# RasPi_Data_Hat.net
KiCad netlist of a schematic drawn in EAGLE
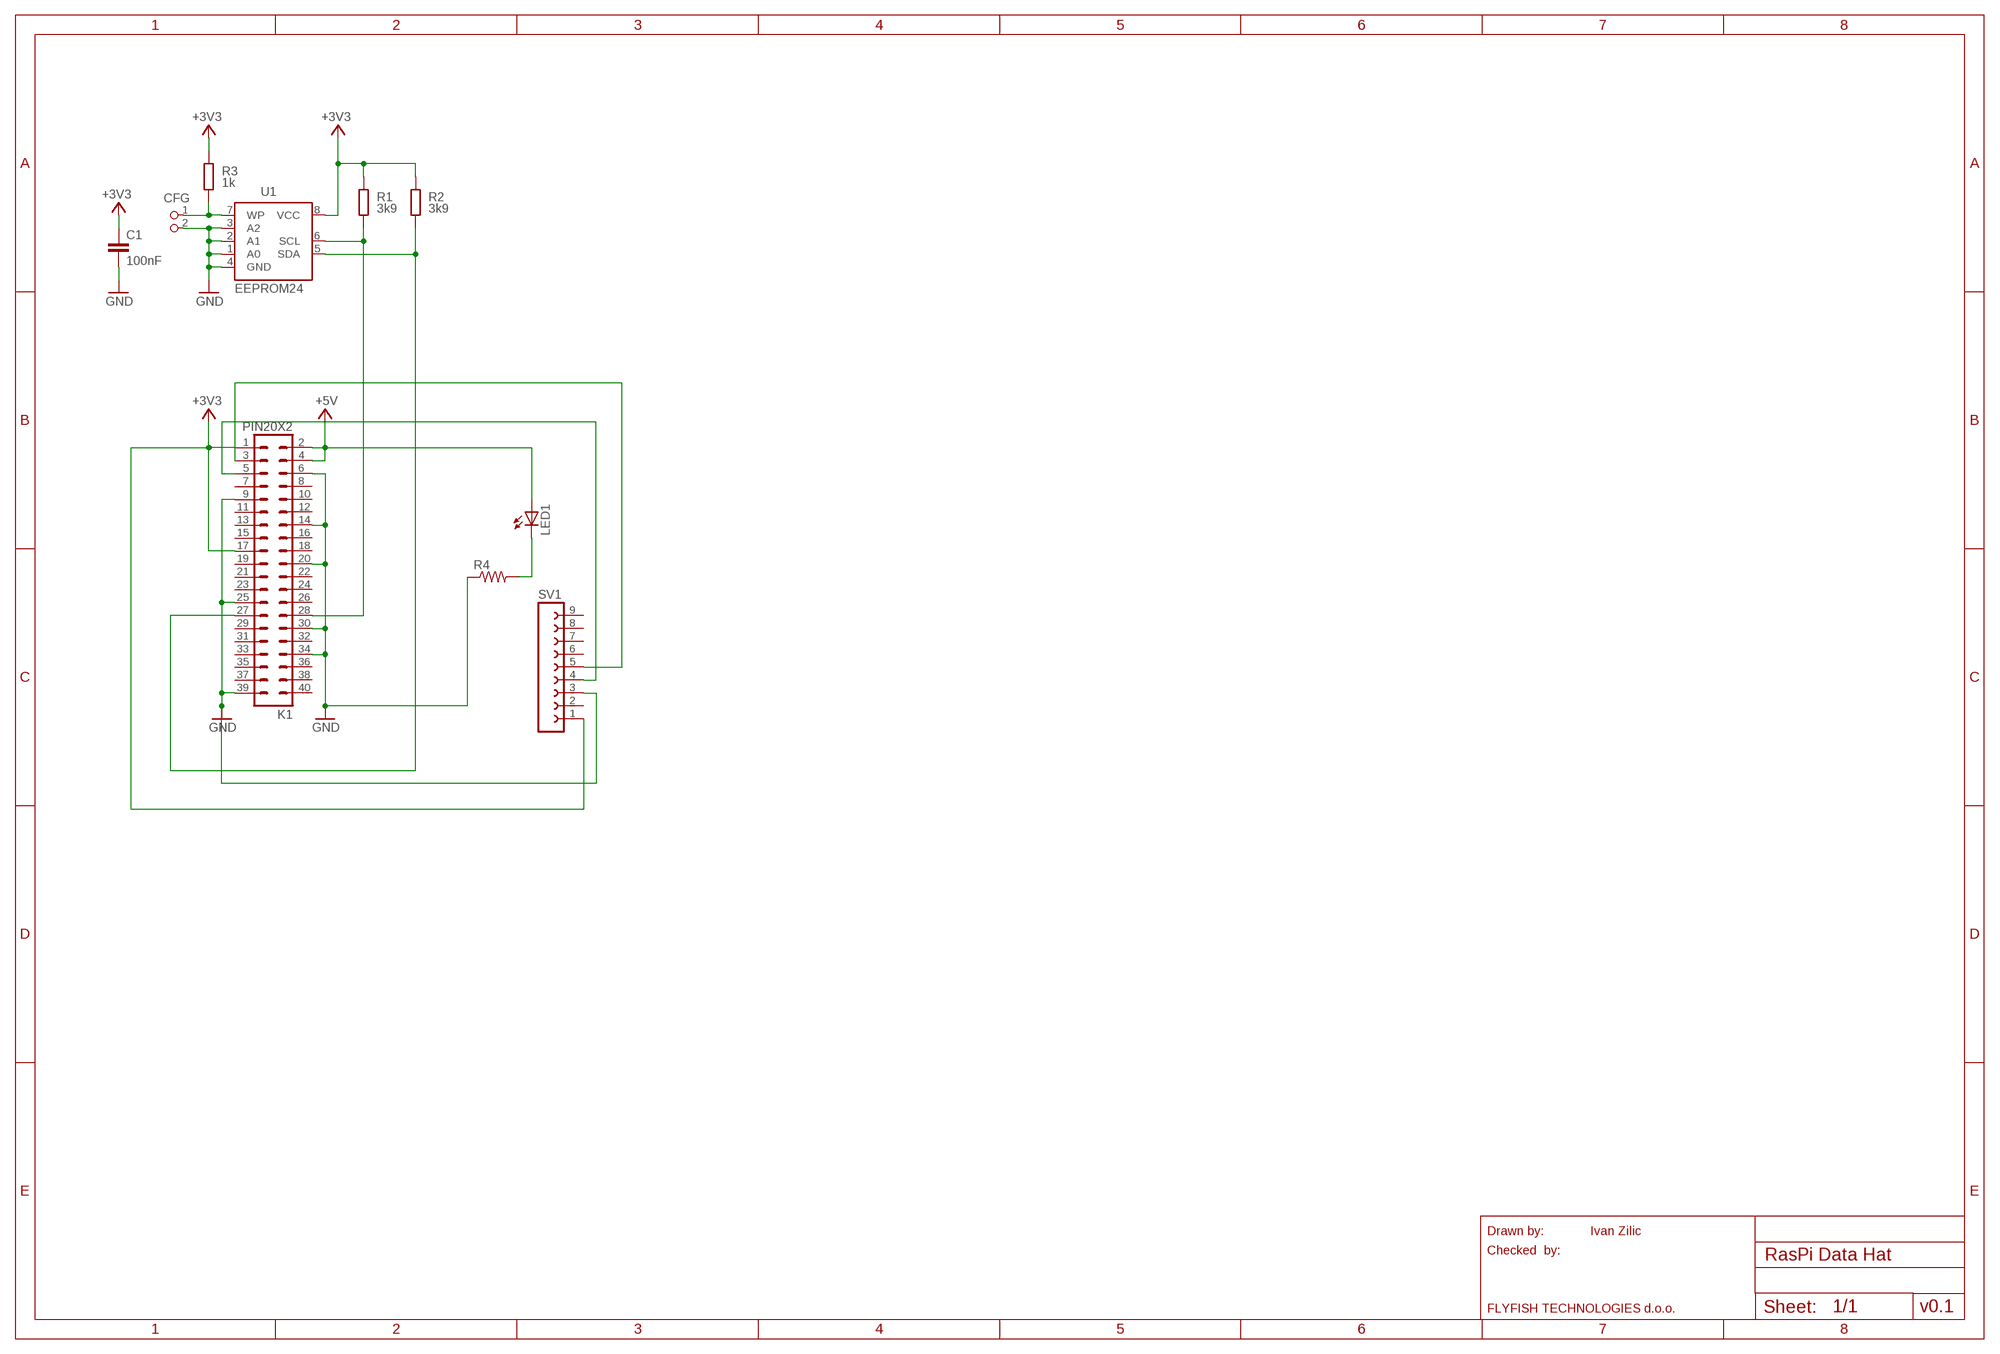
[diagram p0: schematic, sheet 1]

(export (version "E")
  (design (tool "Eeschema 10.0.6"))
  (components
    (comp (ref "C1")
      (value "100nF")
      (footprint "eagle-import:C0805K")
      (libsource (lib "eagle-import") (part "C-EUC0805K"))
    )
    (comp (ref "CFG")
      (value "PIN2_100")
      (footprint "eagle-import:PIN_W_2")
      (libsource (lib "eagle-import") (part "PIN2_100"))
    )
    (comp (ref "K1")
      (value "PIN20X2")
      (footprint "eagle-import:PIN_20X2")
      (libsource (lib "eagle-import") (part "PIN20X2"))
    )
    (comp (ref "LED1")
      (value "LED3MM")
      (footprint "eagle-import:LED3MM")
      (libsource (lib "eagle-import") (part "LED3MM"))
    )
    (comp (ref "R1")
      (value "3k9")
      (footprint "eagle-import:M0805")
      (fields (field (name "TOLERANCE") "5%"))
      (libsource (lib "eagle-import") (part "R-EU_M0805"))
    )
    (comp (ref "R2")
      (value "3k9")
      (footprint "eagle-import:M0805")
      (fields (field (name "TOLERANCE") "5%"))
      (libsource (lib "eagle-import") (part "R-EU_M0805"))
    )
    (comp (ref "R3")
      (value "1k")
      (footprint "eagle-import:M0805")
      (fields (field (name "TOLERANCE") "5%"))
      (libsource (lib "eagle-import") (part "R-EU_M0805"))
    )
    (comp (ref "R4")
      (value "R-US_0204/5")
      (footprint "eagle-import:0204_5")
      (libsource (lib "eagle-import") (part "R-US_0204/5"))
    )
    (comp (ref "SV1")
      (value "FE09-1")
      (footprint "eagle-import:FE09")
      (libsource (lib "eagle-import") (part "FE09-1"))
    )
    (comp (ref "U1")
      (value "EEPROM24")
      (footprint "eagle-import:SOIC8")
      (libsource (lib "eagle-import") (part "EEPROM24"))
    )
  )
  (nets
    (net (code "1") (name "+3V3") (class "Default")
      (node (ref "C1") (pin "1") (pinfunction "1_1") (pintype "passive"))
      (node (ref "K1") (pin "1") (pinfunction "1_1") (pintype "passive"))
      (node (ref "K1") (pin "17") (pinfunction "17_17") (pintype "passive"))
      (node (ref "R1") (pin "2") (pinfunction "2_2") (pintype "passive"))
      (node (ref "R2") (pin "2") (pinfunction "2_2") (pintype "passive"))
      (node (ref "R3") (pin "2") (pinfunction "2_2") (pintype "passive"))
      (node (ref "SV1") (pin "1") (pinfunction "1_1") (pintype "passive"))
      (node (ref "U1") (pin "8") (pinfunction "VCC_8") (pintype "power_in"))
    )
    (net (code "2") (name "+5V") (class "Default")
      (node (ref "K1") (pin "2") (pinfunction "2_2") (pintype "passive"))
      (node (ref "K1") (pin "4") (pinfunction "4_4") (pintype "passive"))
      (node (ref "LED1") (pin "A") (pinfunction "A_A") (pintype "passive"))
    )
    (net (code "3") (name "GND") (class "Default")
      (node (ref "C1") (pin "2") (pinfunction "2_2") (pintype "passive"))
      (node (ref "CFG") (pin "2") (pinfunction "2_2") (pintype "passive"))
      (node (ref "K1") (pin "14") (pinfunction "14_14") (pintype "passive"))
      (node (ref "K1") (pin "20") (pinfunction "20_20") (pintype "passive"))
      (node (ref "K1") (pin "25") (pinfunction "25_25") (pintype "passive"))
      (node (ref "K1") (pin "30") (pinfunction "30_30") (pintype "passive"))
      (node (ref "K1") (pin "34") (pinfunction "34_34") (pintype "passive"))
      (node (ref "K1") (pin "39") (pinfunction "39_39") (pintype "passive"))
      (node (ref "K1") (pin "6") (pinfunction "6_6") (pintype "passive"))
      (node (ref "K1") (pin "9") (pinfunction "9_9") (pintype "passive"))
      (node (ref "R4") (pin "1") (pinfunction "1_1") (pintype "passive"))
      (node (ref "SV1") (pin "3") (pinfunction "3_3") (pintype "passive"))
      (node (ref "U1") (pin "1") (pinfunction "A0_1") (pintype "input"))
      (node (ref "U1") (pin "2") (pinfunction "A1_2") (pintype "input"))
      (node (ref "U1") (pin "3") (pinfunction "A2_3") (pintype "input"))
      (node (ref "U1") (pin "4") (pinfunction "GND_4") (pintype "power_in"))
    )
    (net (code "4") (name "Net-(K1-Pad3)") (class "Default")
      (node (ref "K1") (pin "3") (pinfunction "3_3") (pintype "passive"))
      (node (ref "SV1") (pin "5") (pinfunction "5_5") (pintype "passive"))
    )
    (net (code "5") (name "Net-(K1-Pad5)") (class "Default")
      (node (ref "K1") (pin "5") (pinfunction "5_5") (pintype "passive"))
      (node (ref "SV1") (pin "4") (pinfunction "4_4") (pintype "passive"))
    )
    (net (code "6") (name "Net-(LED1-C)") (class "Default")
      (node (ref "LED1") (pin "K") (pinfunction "C_K") (pintype "passive"))
      (node (ref "R4") (pin "2") (pinfunction "2_2") (pintype "passive"))
    )
    (net (code "7") (name "Net-(U1-SCL)") (class "Default")
      (node (ref "K1") (pin "28") (pinfunction "28_28") (pintype "passive"))
      (node (ref "R1") (pin "1") (pinfunction "1_1") (pintype "passive"))
      (node (ref "U1") (pin "6") (pinfunction "SCL_6") (pintype "input"))
    )
    (net (code "8") (name "Net-(U1-SDA)") (class "Default")
      (node (ref "K1") (pin "27") (pinfunction "27_27") (pintype "passive"))
      (node (ref "R2") (pin "1") (pinfunction "1_1") (pintype "passive"))
      (node (ref "U1") (pin "5") (pinfunction "SDA_5") (pintype "bidirectional"))
    )
    (net (code "9") (name "Net-(U1-WP)") (class "Default")
      (node (ref "CFG") (pin "1") (pinfunction "1_1") (pintype "passive"))
      (node (ref "R3") (pin "1") (pinfunction "1_1") (pintype "passive"))
      (node (ref "U1") (pin "7") (pinfunction "WP_7") (pintype "input"))
    )
    (net (code "10") (name "unconnected-(K1-Pad7)") (class "Default")
      (node (ref "K1") (pin "7") (pinfunction "7_7") (pintype "passive"))
    )
    (net (code "11") (name "unconnected-(K1-Pad8)") (class "Default")
      (node (ref "K1") (pin "8") (pinfunction "8_8") (pintype "passive"))
    )
    (net (code "12") (name "unconnected-(K1-Pad10)") (class "Default")
      (node (ref "K1") (pin "10") (pinfunction "10_10") (pintype "passive"))
    )
    (net (code "13") (name "unconnected-(K1-Pad11)") (class "Default")
      (node (ref "K1") (pin "11") (pinfunction "11_11") (pintype "passive"))
    )
    (net (code "14") (name "unconnected-(K1-Pad12)") (class "Default")
      (node (ref "K1") (pin "12") (pinfunction "12_12") (pintype "passive"))
    )
    (net (code "15") (name "unconnected-(K1-Pad13)") (class "Default")
      (node (ref "K1") (pin "13") (pinfunction "13_13") (pintype "passive"))
    )
    (net (code "16") (name "unconnected-(K1-Pad15)") (class "Default")
      (node (ref "K1") (pin "15") (pinfunction "15_15") (pintype "passive"))
    )
    (net (code "17") (name "unconnected-(K1-Pad16)") (class "Default")
      (node (ref "K1") (pin "16") (pinfunction "16_16") (pintype "passive"))
    )
    (net (code "18") (name "unconnected-(K1-Pad18)") (class "Default")
      (node (ref "K1") (pin "18") (pinfunction "18_18") (pintype "passive"))
    )
    (net (code "19") (name "unconnected-(K1-Pad19)") (class "Default")
      (node (ref "K1") (pin "19") (pinfunction "19_19") (pintype "passive"))
    )
    (net (code "20") (name "unconnected-(K1-Pad21)") (class "Default")
      (node (ref "K1") (pin "21") (pinfunction "21_21") (pintype "passive"))
    )
    (net (code "21") (name "unconnected-(K1-Pad22)") (class "Default")
      (node (ref "K1") (pin "22") (pinfunction "22_22") (pintype "passive"))
    )
    (net (code "22") (name "unconnected-(K1-Pad23)") (class "Default")
      (node (ref "K1") (pin "23") (pinfunction "23_23") (pintype "passive"))
    )
    (net (code "23") (name "unconnected-(K1-Pad24)") (class "Default")
      (node (ref "K1") (pin "24") (pinfunction "24_24") (pintype "passive"))
    )
    (net (code "24") (name "unconnected-(K1-Pad26)") (class "Default")
      (node (ref "K1") (pin "26") (pinfunction "26_26") (pintype "passive"))
    )
    (net (code "25") (name "unconnected-(K1-Pad29)") (class "Default")
      (node (ref "K1") (pin "29") (pinfunction "29_29") (pintype "passive"))
    )
    (net (code "26") (name "unconnected-(K1-Pad31)") (class "Default")
      (node (ref "K1") (pin "31") (pinfunction "31_31") (pintype "passive"))
    )
    (net (code "27") (name "unconnected-(K1-Pad32)") (class "Default")
      (node (ref "K1") (pin "32") (pinfunction "32_32") (pintype "passive"))
    )
    (net (code "28") (name "unconnected-(K1-Pad33)") (class "Default")
      (node (ref "K1") (pin "33") (pinfunction "33_33") (pintype "passive"))
    )
    (net (code "29") (name "unconnected-(K1-Pad35)") (class "Default")
      (node (ref "K1") (pin "35") (pinfunction "35_35") (pintype "passive"))
    )
    (net (code "30") (name "unconnected-(K1-Pad36)") (class "Default")
      (node (ref "K1") (pin "36") (pinfunction "36_36") (pintype "passive"))
    )
    (net (code "31") (name "unconnected-(K1-Pad37)") (class "Default")
      (node (ref "K1") (pin "37") (pinfunction "37_37") (pintype "passive"))
    )
    (net (code "32") (name "unconnected-(K1-Pad38)") (class "Default")
      (node (ref "K1") (pin "38") (pinfunction "38_38") (pintype "passive"))
    )
    (net (code "33") (name "unconnected-(K1-Pad40)") (class "Default")
      (node (ref "K1") (pin "40") (pinfunction "40_40") (pintype "passive"))
    )
    (net (code "34") (name "unconnected-(SV1-Pad2)") (class "Default")
      (node (ref "SV1") (pin "2") (pinfunction "2_2") (pintype "passive"))
    )
    (net (code "35") (name "unconnected-(SV1-Pad6)") (class "Default")
      (node (ref "SV1") (pin "6") (pinfunction "6_6") (pintype "passive"))
    )
    (net (code "36") (name "unconnected-(SV1-Pad7)") (class "Default")
      (node (ref "SV1") (pin "7") (pinfunction "7_7") (pintype "passive"))
    )
    (net (code "37") (name "unconnected-(SV1-Pad8)") (class "Default")
      (node (ref "SV1") (pin "8") (pinfunction "8_8") (pintype "passive"))
    )
    (net (code "38") (name "unconnected-(SV1-Pad9)") (class "Default")
      (node (ref "SV1") (pin "9") (pinfunction "9_9") (pintype "passive"))
    )
  )
)
